# ekspres_led.net
KiCad netlist of a schematic drawn in EAGLE
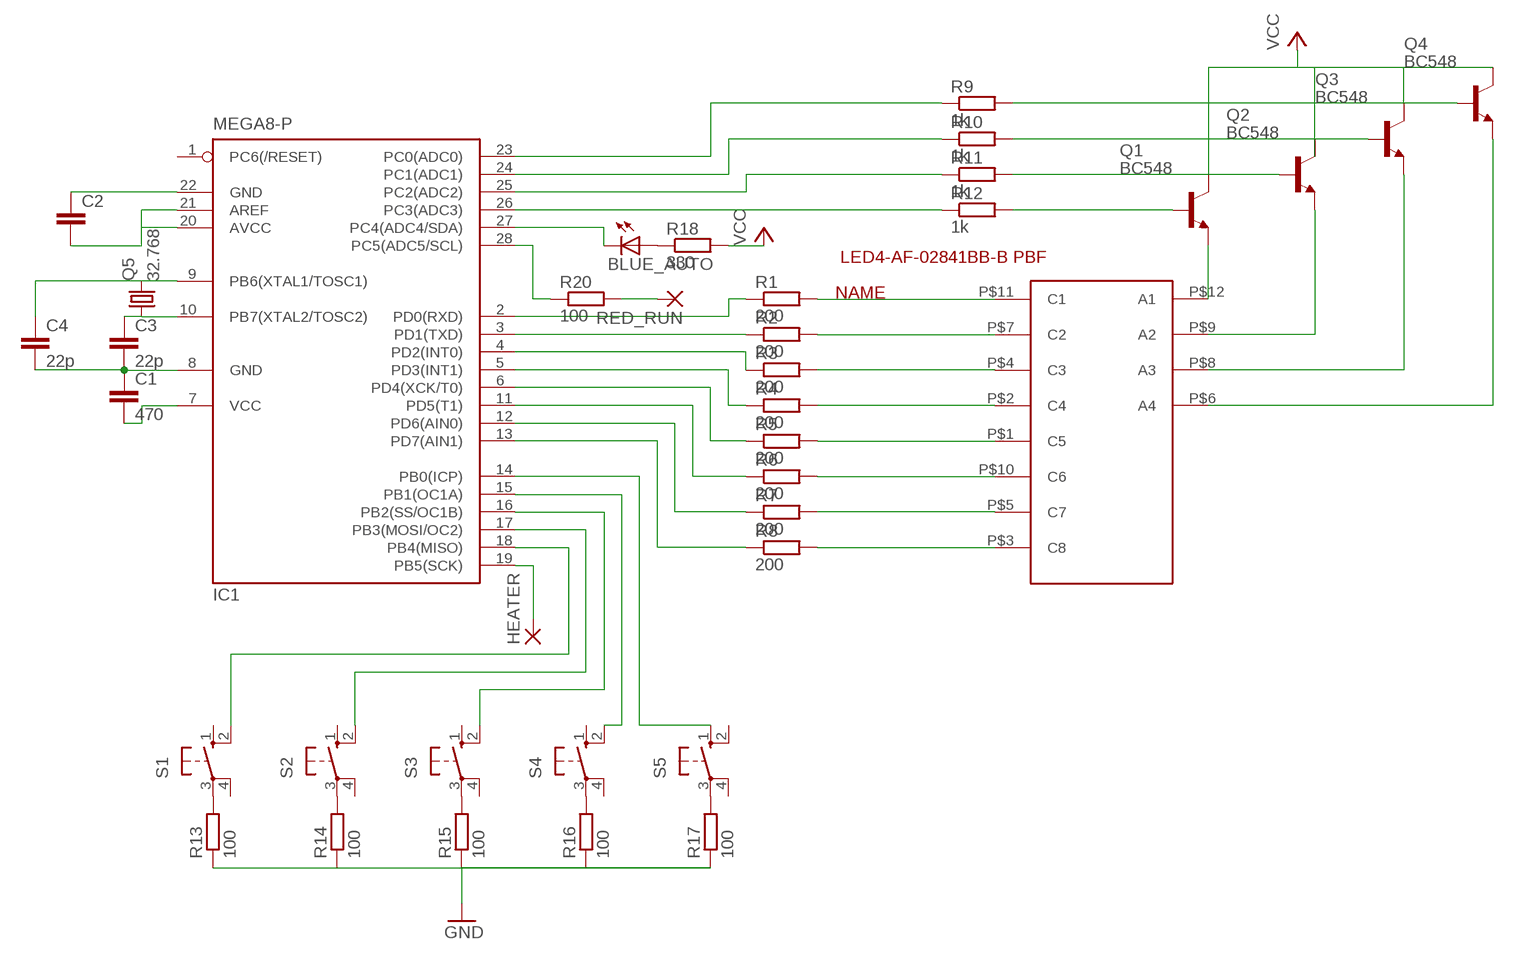
[diagram p0: schematic, sheet 1]

(export (version "E")
  (design (tool "Eeschema 10.0.6"))
  (components
    (comp (ref "BLUE_AUTO")
      (value "LED5MM")
      (footprint "eagle-import:LED5MM")
      (libsource (lib "eagle-import") (part "LED5MM"))
    )
    (comp (ref "C1")
      (value "470")
      (footprint "eagle-import:C025-025X050")
      (libsource (lib "eagle-import") (part "C-EU025-025X050"))
    )
    (comp (ref "C2")
      (value "C-EU025-025X050")
      (footprint "eagle-import:C025-025X050")
      (libsource (lib "eagle-import") (part "C-EU025-025X050"))
    )
    (comp (ref "C3")
      (value "22p")
      (footprint "eagle-import:C025-025X050")
      (libsource (lib "eagle-import") (part "C-EU025-025X050"))
    )
    (comp (ref "C4")
      (value "22p")
      (footprint "eagle-import:C025-025X050")
      (libsource (lib "eagle-import") (part "C-EU025-025X050"))
    )
    (comp (ref "DISPLAY")
      (value "LED4-AF-02841BB-B")
      (footprint "eagle-import:LED4-AF-02841BB-B")
      (libsource (lib "eagle-import") (part "LED4-AF-02841BB-B"))
    )
    (comp (ref "HEATER")
      (value "1,6/0,8")
      (footprint "eagle-import:1,6_0,8")
      (libsource (lib "eagle-import") (part "1,6/0,8"))
    )
    (comp (ref "IC1")
      (value "MEGA8-P")
      (footprint "eagle-import:DIL28-3")
      (libsource (lib "eagle-import") (part "MEGA8-P"))
    )
    (comp (ref "Q1")
      (value "BC548")
      (footprint "eagle-import:TO92-EBC")
      (libsource (lib "eagle-import") (part "BC548"))
    )
    (comp (ref "Q2")
      (value "BC548")
      (footprint "eagle-import:TO92-EBC")
      (libsource (lib "eagle-import") (part "BC548"))
    )
    (comp (ref "Q3")
      (value "BC548")
      (footprint "eagle-import:TO92-EBC")
      (libsource (lib "eagle-import") (part "BC548"))
    )
    (comp (ref "Q4")
      (value "BC548")
      (footprint "eagle-import:TO92-EBC")
      (libsource (lib "eagle-import") (part "BC548"))
    )
    (comp (ref "Q5")
      (value "32.768")
      (footprint "eagle-import:TC38H")
      (libsource (lib "eagle-import") (part "CRYSTALTC38H"))
    )
    (comp (ref "R1")
      (value "200")
      (footprint "eagle-import:0204_7")
      (libsource (lib "eagle-import") (part "R-EU_0204/7"))
    )
    (comp (ref "R2")
      (value "200")
      (footprint "eagle-import:0204_7")
      (libsource (lib "eagle-import") (part "R-EU_0204/7"))
    )
    (comp (ref "R3")
      (value "200")
      (footprint "eagle-import:0204_7")
      (libsource (lib "eagle-import") (part "R-EU_0204/7"))
    )
    (comp (ref "R4")
      (value "200")
      (footprint "eagle-import:0204_7")
      (libsource (lib "eagle-import") (part "R-EU_0204/7"))
    )
    (comp (ref "R5")
      (value "200")
      (footprint "eagle-import:0204_7")
      (libsource (lib "eagle-import") (part "R-EU_0204/7"))
    )
    (comp (ref "R6")
      (value "200")
      (footprint "eagle-import:0204_7")
      (libsource (lib "eagle-import") (part "R-EU_0204/7"))
    )
    (comp (ref "R7")
      (value "200")
      (footprint "eagle-import:0204_7")
      (libsource (lib "eagle-import") (part "R-EU_0204/7"))
    )
    (comp (ref "R8")
      (value "200")
      (footprint "eagle-import:0204_7")
      (libsource (lib "eagle-import") (part "R-EU_0204/7"))
    )
    (comp (ref "R9")
      (value "1k")
      (footprint "eagle-import:0204_7")
      (libsource (lib "eagle-import") (part "R-EU_0204/7"))
    )
    (comp (ref "R10")
      (value "1k")
      (footprint "eagle-import:0204_7")
      (libsource (lib "eagle-import") (part "R-EU_0204/7"))
    )
    (comp (ref "R11")
      (value "1k")
      (footprint "eagle-import:0204_7")
      (libsource (lib "eagle-import") (part "R-EU_0204/7"))
    )
    (comp (ref "R12")
      (value "1k")
      (footprint "eagle-import:0204_7")
      (libsource (lib "eagle-import") (part "R-EU_0204/7"))
    )
    (comp (ref "R13")
      (value "100")
      (footprint "eagle-import:0204_5")
      (libsource (lib "eagle-import") (part "R-EU_0204/5"))
    )
    (comp (ref "R14")
      (value "100")
      (footprint "eagle-import:0204_5")
      (libsource (lib "eagle-import") (part "R-EU_0204/5"))
    )
    (comp (ref "R15")
      (value "100")
      (footprint "eagle-import:0204_5")
      (libsource (lib "eagle-import") (part "R-EU_0204/5"))
    )
    (comp (ref "R16")
      (value "100")
      (footprint "eagle-import:0204_5")
      (libsource (lib "eagle-import") (part "R-EU_0204/5"))
    )
    (comp (ref "R17")
      (value "100")
      (footprint "eagle-import:0204_5")
      (libsource (lib "eagle-import") (part "R-EU_0204/5"))
    )
    (comp (ref "R18")
      (value "330")
      (footprint "eagle-import:0204_7")
      (libsource (lib "eagle-import") (part "R-EU_0204/7"))
    )
    (comp (ref "R20")
      (value "100")
      (footprint "eagle-import:0204_7")
      (libsource (lib "eagle-import") (part "R-EU_0204/7"))
    )
    (comp (ref "RED_RUN")
      (value "1,6/0,8")
      (footprint "eagle-import:1,6_0,8")
      (libsource (lib "eagle-import") (part "1,6/0,8"))
    )
    (comp (ref "S1")
      (value "10-XX")
      (footprint "eagle-import:B3F-10XX")
      (fields (field (name "MPN") "B3F-1000"))
      (libsource (lib "eagle-import") (part "10-XX"))
    )
    (comp (ref "S2")
      (value "10-XX")
      (footprint "eagle-import:B3F-10XX")
      (fields (field (name "MPN") "B3F-1000"))
      (libsource (lib "eagle-import") (part "10-XX"))
    )
    (comp (ref "S3")
      (value "10-XX")
      (footprint "eagle-import:B3F-10XX")
      (fields (field (name "MPN") "B3F-1000"))
      (libsource (lib "eagle-import") (part "10-XX"))
    )
    (comp (ref "S4")
      (value "10-XX")
      (footprint "eagle-import:B3F-10XX")
      (fields (field (name "MPN") "B3F-1000"))
      (libsource (lib "eagle-import") (part "10-XX"))
    )
    (comp (ref "S5")
      (value "10-XX")
      (footprint "eagle-import:B3F-10XX")
      (fields (field (name "MPN") "B3F-1000"))
      (libsource (lib "eagle-import") (part "10-XX"))
    )
  )
  (nets
    (net (code "1") (name "GND") (class "Default")
      (node (ref "C1") (pin "1") (pinfunction "1_1") (pintype "passive"))
      (node (ref "C2") (pin "1") (pinfunction "1_1") (pintype "passive"))
      (node (ref "C3") (pin "2") (pinfunction "2_2") (pintype "passive"))
      (node (ref "C4") (pin "2") (pinfunction "2_2") (pintype "passive"))
      (node (ref "IC1") (pin "22") (pinfunction "GND_22") (pintype "power_in"))
      (node (ref "IC1") (pin "8") (pinfunction "GND_8") (pintype "power_in"))
      (node (ref "R13") (pin "1") (pinfunction "1_1") (pintype "passive"))
      (node (ref "R14") (pin "1") (pinfunction "1_1") (pintype "passive"))
      (node (ref "R15") (pin "1") (pinfunction "1_1") (pintype "passive"))
      (node (ref "R16") (pin "1") (pinfunction "1_1") (pintype "passive"))
      (node (ref "R17") (pin "1") (pinfunction "1_1") (pintype "passive"))
    )
    (net (code "2") (name "Net-(BLUE_AUTO-C)") (class "Default")
      (node (ref "BLUE_AUTO") (pin "K") (pinfunction "C_K") (pintype "passive"))
      (node (ref "IC1") (pin "27") (pinfunction "PC4(ADC4/SDA)_27") (pintype "bidirectional"))
    )
    (net (code "3") (name "Net-(BLUE_AUTO-PadA)") (class "Default")
      (node (ref "BLUE_AUTO") (pin "A") (pinfunction "A_A") (pintype "passive"))
      (node (ref "R18") (pin "1") (pinfunction "1_1") (pintype "passive"))
    )
    (net (code "4") (name "Net-(DISPLAY-A1)") (class "Default")
      (node (ref "DISPLAY") (pin "P$12") (pinfunction "A1_P$12") (pintype "bidirectional"))
      (node (ref "Q1") (pin "E") (pinfunction "E_E") (pintype "passive"))
    )
    (net (code "5") (name "Net-(DISPLAY-A2)") (class "Default")
      (node (ref "DISPLAY") (pin "P$9") (pinfunction "A2_P$9") (pintype "bidirectional"))
      (node (ref "Q2") (pin "E") (pinfunction "E_E") (pintype "passive"))
    )
    (net (code "6") (name "Net-(DISPLAY-A3)") (class "Default")
      (node (ref "DISPLAY") (pin "P$8") (pinfunction "A3_P$8") (pintype "bidirectional"))
      (node (ref "Q3") (pin "E") (pinfunction "E_E") (pintype "passive"))
    )
    (net (code "7") (name "Net-(DISPLAY-A4)") (class "Default")
      (node (ref "DISPLAY") (pin "P$6") (pinfunction "A4_P$6") (pintype "bidirectional"))
      (node (ref "Q4") (pin "E") (pinfunction "E_E") (pintype "passive"))
    )
    (net (code "8") (name "Net-(DISPLAY-C1)") (class "Default")
      (node (ref "DISPLAY") (pin "P$11") (pinfunction "C1_P$11") (pintype "bidirectional"))
      (node (ref "R1") (pin "2") (pinfunction "2_2") (pintype "passive"))
    )
    (net (code "9") (name "Net-(DISPLAY-C2)") (class "Default")
      (node (ref "DISPLAY") (pin "P$7") (pinfunction "C2_P$7") (pintype "bidirectional"))
      (node (ref "R2") (pin "2") (pinfunction "2_2") (pintype "passive"))
    )
    (net (code "10") (name "Net-(DISPLAY-C3)") (class "Default")
      (node (ref "DISPLAY") (pin "P$4") (pinfunction "C3_P$4") (pintype "bidirectional"))
      (node (ref "R3") (pin "2") (pinfunction "2_2") (pintype "passive"))
    )
    (net (code "11") (name "Net-(DISPLAY-C4)") (class "Default")
      (node (ref "DISPLAY") (pin "P$2") (pinfunction "C4_P$2") (pintype "bidirectional"))
      (node (ref "R4") (pin "2") (pinfunction "2_2") (pintype "passive"))
    )
    (net (code "12") (name "Net-(DISPLAY-C5)") (class "Default")
      (node (ref "DISPLAY") (pin "P$1") (pinfunction "C5_P$1") (pintype "bidirectional"))
      (node (ref "R5") (pin "2") (pinfunction "2_2") (pintype "passive"))
    )
    (net (code "13") (name "Net-(DISPLAY-C6)") (class "Default")
      (node (ref "DISPLAY") (pin "P$10") (pinfunction "C6_P$10") (pintype "bidirectional"))
      (node (ref "R6") (pin "2") (pinfunction "2_2") (pintype "passive"))
    )
    (net (code "14") (name "Net-(DISPLAY-C7)") (class "Default")
      (node (ref "DISPLAY") (pin "P$5") (pinfunction "C7_P$5") (pintype "bidirectional"))
      (node (ref "R7") (pin "2") (pinfunction "2_2") (pintype "passive"))
    )
    (net (code "15") (name "Net-(DISPLAY-C8)") (class "Default")
      (node (ref "DISPLAY") (pin "P$3") (pinfunction "C8_P$3") (pintype "bidirectional"))
      (node (ref "R8") (pin "2") (pinfunction "2_2") (pintype "passive"))
    )
    (net (code "16") (name "Net-(HEATER-P)") (class "Default")
      (node (ref "HEATER") (pin "1") (pinfunction "P_1") (pintype "passive"))
      (node (ref "IC1") (pin "19") (pinfunction "PB5(SCK)_19") (pintype "bidirectional"))
    )
    (net (code "17") (name "Net-(IC1-PB0(ICP))") (class "Default")
      (node (ref "IC1") (pin "14") (pinfunction "PB0(ICP)_14") (pintype "bidirectional"))
      (node (ref "S5") (pin "1") (pinfunction "S_1") (pintype "passive"))
    )
    (net (code "18") (name "Net-(IC1-PB1(OC1A))") (class "Default")
      (node (ref "IC1") (pin "15") (pinfunction "PB1(OC1A)_15") (pintype "bidirectional"))
      (node (ref "S4") (pin "2") (pinfunction "S1_2") (pintype "passive"))
    )
    (net (code "19") (name "Net-(IC1-PB2(SS{slash}OC1B))") (class "Default")
      (node (ref "IC1") (pin "16") (pinfunction "PB2(SS/OC1B)_16") (pintype "bidirectional"))
      (node (ref "S3") (pin "2") (pinfunction "S1_2") (pintype "passive"))
    )
    (net (code "20") (name "Net-(IC1-PB3(MOSI{slash}OC2))") (class "Default")
      (node (ref "IC1") (pin "17") (pinfunction "PB3(MOSI/OC2)_17") (pintype "bidirectional"))
      (node (ref "S2") (pin "2") (pinfunction "S1_2") (pintype "passive"))
    )
    (net (code "21") (name "Net-(IC1-PB4(MISO))") (class "Default")
      (node (ref "IC1") (pin "18") (pinfunction "PB4(MISO)_18") (pintype "bidirectional"))
      (node (ref "S1") (pin "2") (pinfunction "S1_2") (pintype "passive"))
    )
    (net (code "22") (name "Net-(IC1-PB6(XTAL1{slash}TOSC1))") (class "Default")
      (node (ref "C4") (pin "1") (pinfunction "1_1") (pintype "passive"))
      (node (ref "IC1") (pin "9") (pinfunction "PB6(XTAL1/TOSC1)_9") (pintype "bidirectional"))
      (node (ref "Q5") (pin "2") (pinfunction "2_2") (pintype "passive"))
    )
    (net (code "23") (name "Net-(IC1-PB7(XTAL2{slash}TOSC2))") (class "Default")
      (node (ref "C3") (pin "1") (pinfunction "1_1") (pintype "passive"))
      (node (ref "IC1") (pin "10") (pinfunction "PB7(XTAL2/TOSC2)_10") (pintype "bidirectional"))
      (node (ref "Q5") (pin "1") (pinfunction "1_1") (pintype "passive"))
    )
    (net (code "24") (name "Net-(IC1-PC0(ADC0))") (class "Default")
      (node (ref "IC1") (pin "23") (pinfunction "PC0(ADC0)_23") (pintype "bidirectional"))
      (node (ref "R9") (pin "1") (pinfunction "1_1") (pintype "passive"))
    )
    (net (code "25") (name "Net-(IC1-PC1(ADC1))") (class "Default")
      (node (ref "IC1") (pin "24") (pinfunction "PC1(ADC1)_24") (pintype "bidirectional"))
      (node (ref "R10") (pin "1") (pinfunction "1_1") (pintype "passive"))
    )
    (net (code "26") (name "Net-(IC1-PC2(ADC2))") (class "Default")
      (node (ref "IC1") (pin "25") (pinfunction "PC2(ADC2)_25") (pintype "bidirectional"))
      (node (ref "R11") (pin "1") (pinfunction "1_1") (pintype "passive"))
    )
    (net (code "27") (name "Net-(IC1-PC3(ADC3))") (class "Default")
      (node (ref "IC1") (pin "26") (pinfunction "PC3(ADC3)_26") (pintype "bidirectional"))
      (node (ref "R12") (pin "1") (pinfunction "1_1") (pintype "passive"))
    )
    (net (code "28") (name "Net-(IC1-PC5(ADC5{slash}SCL))") (class "Default")
      (node (ref "IC1") (pin "28") (pinfunction "PC5(ADC5/SCL)_28") (pintype "bidirectional"))
      (node (ref "R20") (pin "1") (pinfunction "1_1") (pintype "passive"))
    )
    (net (code "29") (name "Net-(IC1-PD0(RXD))") (class "Default")
      (node (ref "IC1") (pin "2") (pinfunction "PD0(RXD)_2") (pintype "bidirectional"))
      (node (ref "R1") (pin "1") (pinfunction "1_1") (pintype "passive"))
    )
    (net (code "30") (name "Net-(IC1-PD1(TXD))") (class "Default")
      (node (ref "IC1") (pin "3") (pinfunction "PD1(TXD)_3") (pintype "bidirectional"))
      (node (ref "R2") (pin "1") (pinfunction "1_1") (pintype "passive"))
    )
    (net (code "31") (name "Net-(IC1-PD2(INT0))") (class "Default")
      (node (ref "IC1") (pin "4") (pinfunction "PD2(INT0)_4") (pintype "bidirectional"))
      (node (ref "R3") (pin "1") (pinfunction "1_1") (pintype "passive"))
    )
    (net (code "32") (name "Net-(IC1-PD3(INT1))") (class "Default")
      (node (ref "IC1") (pin "5") (pinfunction "PD3(INT1)_5") (pintype "bidirectional"))
      (node (ref "R4") (pin "1") (pinfunction "1_1") (pintype "passive"))
    )
    (net (code "33") (name "Net-(IC1-PD4(XCK{slash}T0))") (class "Default")
      (node (ref "IC1") (pin "6") (pinfunction "PD4(XCK/T0)_6") (pintype "bidirectional"))
      (node (ref "R5") (pin "1") (pinfunction "1_1") (pintype "passive"))
    )
    (net (code "34") (name "Net-(IC1-PD5(T1))") (class "Default")
      (node (ref "IC1") (pin "11") (pinfunction "PD5(T1)_11") (pintype "bidirectional"))
      (node (ref "R6") (pin "1") (pinfunction "1_1") (pintype "passive"))
    )
    (net (code "35") (name "Net-(IC1-PD6(AIN0))") (class "Default")
      (node (ref "IC1") (pin "12") (pinfunction "PD6(AIN0)_12") (pintype "bidirectional"))
      (node (ref "R7") (pin "1") (pinfunction "1_1") (pintype "passive"))
    )
    (net (code "36") (name "Net-(IC1-PD7(AIN1))") (class "Default")
      (node (ref "IC1") (pin "13") (pinfunction "PD7(AIN1)_13") (pintype "bidirectional"))
      (node (ref "R8") (pin "1") (pinfunction "1_1") (pintype "passive"))
    )
    (net (code "37") (name "Net-(Q1-PadB)") (class "Default")
      (node (ref "Q1") (pin "B") (pinfunction "B_B") (pintype "passive"))
      (node (ref "R12") (pin "2") (pinfunction "2_2") (pintype "passive"))
    )
    (net (code "38") (name "Net-(Q2-PadB)") (class "Default")
      (node (ref "Q2") (pin "B") (pinfunction "B_B") (pintype "passive"))
      (node (ref "R11") (pin "2") (pinfunction "2_2") (pintype "passive"))
    )
    (net (code "39") (name "Net-(Q3-PadB)") (class "Default")
      (node (ref "Q3") (pin "B") (pinfunction "B_B") (pintype "passive"))
      (node (ref "R10") (pin "2") (pinfunction "2_2") (pintype "passive"))
    )
    (net (code "40") (name "Net-(Q4-PadB)") (class "Default")
      (node (ref "Q4") (pin "B") (pinfunction "B_B") (pintype "passive"))
      (node (ref "R9") (pin "2") (pinfunction "2_2") (pintype "passive"))
    )
    (net (code "41") (name "Net-(RED_RUN-P)") (class "Default")
      (node (ref "R20") (pin "2") (pinfunction "2_2") (pintype "passive"))
      (node (ref "RED_RUN") (pin "1") (pinfunction "P_1") (pintype "passive"))
    )
    (net (code "42") (name "Net-(S1-P)") (class "Default")
      (node (ref "R13") (pin "2") (pinfunction "2_2") (pintype "passive"))
      (node (ref "S1") (pin "3") (pinfunction "P_3") (pintype "passive"))
    )
    (net (code "43") (name "Net-(S2-P)") (class "Default")
      (node (ref "R14") (pin "2") (pinfunction "2_2") (pintype "passive"))
      (node (ref "S2") (pin "3") (pinfunction "P_3") (pintype "passive"))
    )
    (net (code "44") (name "Net-(S3-P)") (class "Default")
      (node (ref "R15") (pin "2") (pinfunction "2_2") (pintype "passive"))
      (node (ref "S3") (pin "3") (pinfunction "P_3") (pintype "passive"))
    )
    (net (code "45") (name "Net-(S4-P)") (class "Default")
      (node (ref "R16") (pin "2") (pinfunction "2_2") (pintype "passive"))
      (node (ref "S4") (pin "3") (pinfunction "P_3") (pintype "passive"))
    )
    (net (code "46") (name "Net-(S5-P)") (class "Default")
      (node (ref "R17") (pin "2") (pinfunction "2_2") (pintype "passive"))
      (node (ref "S5") (pin "3") (pinfunction "P_3") (pintype "passive"))
    )
    (net (code "47") (name "VCC") (class "Default")
      (node (ref "C1") (pin "2") (pinfunction "2_2") (pintype "passive"))
      (node (ref "C2") (pin "2") (pinfunction "2_2") (pintype "passive"))
      (node (ref "IC1") (pin "20") (pinfunction "AVCC_20") (pintype "power_in"))
      (node (ref "IC1") (pin "21") (pinfunction "AREF_21") (pintype "passive"))
      (node (ref "IC1") (pin "7") (pinfunction "VCC_7") (pintype "power_in"))
      (node (ref "Q1") (pin "C") (pinfunction "C_C") (pintype "passive"))
      (node (ref "Q2") (pin "C") (pinfunction "C_C") (pintype "passive"))
      (node (ref "Q3") (pin "C") (pinfunction "C_C") (pintype "passive"))
      (node (ref "Q4") (pin "C") (pinfunction "C_C") (pintype "passive"))
      (node (ref "R18") (pin "2") (pinfunction "2_2") (pintype "passive"))
    )
    (net (code "48") (name "unconnected-(IC1-PC6({slash}RESET)-Pad1)") (class "Default")
      (node (ref "IC1") (pin "1") (pinfunction "PC6(/RESET)_1") (pintype "bidirectional"))
    )
    (net (code "49") (name "unconnected-(S1-P1-Pad4)") (class "Default")
      (node (ref "S1") (pin "4") (pinfunction "P1_4") (pintype "passive"))
    )
    (net (code "50") (name "unconnected-(S1-S-Pad1)") (class "Default")
      (node (ref "S1") (pin "1") (pinfunction "S_1") (pintype "passive"))
    )
    (net (code "51") (name "unconnected-(S2-P1-Pad4)") (class "Default")
      (node (ref "S2") (pin "4") (pinfunction "P1_4") (pintype "passive"))
    )
    (net (code "52") (name "unconnected-(S2-S-Pad1)") (class "Default")
      (node (ref "S2") (pin "1") (pinfunction "S_1") (pintype "passive"))
    )
    (net (code "53") (name "unconnected-(S3-P1-Pad4)") (class "Default")
      (node (ref "S3") (pin "4") (pinfunction "P1_4") (pintype "passive"))
    )
    (net (code "54") (name "unconnected-(S3-S-Pad1)") (class "Default")
      (node (ref "S3") (pin "1") (pinfunction "S_1") (pintype "passive"))
    )
    (net (code "55") (name "unconnected-(S4-P1-Pad4)") (class "Default")
      (node (ref "S4") (pin "4") (pinfunction "P1_4") (pintype "passive"))
    )
    (net (code "56") (name "unconnected-(S4-S-Pad1)") (class "Default")
      (node (ref "S4") (pin "1") (pinfunction "S_1") (pintype "passive"))
    )
    (net (code "57") (name "unconnected-(S5-P1-Pad4)") (class "Default")
      (node (ref "S5") (pin "4") (pinfunction "P1_4") (pintype "passive"))
    )
    (net (code "58") (name "unconnected-(S5-S1-Pad2)") (class "Default")
      (node (ref "S5") (pin "2") (pinfunction "S1_2") (pintype "passive"))
    )
  )
)
